# User.net
KiCad netlist of a schematic drawn in Altium Designer
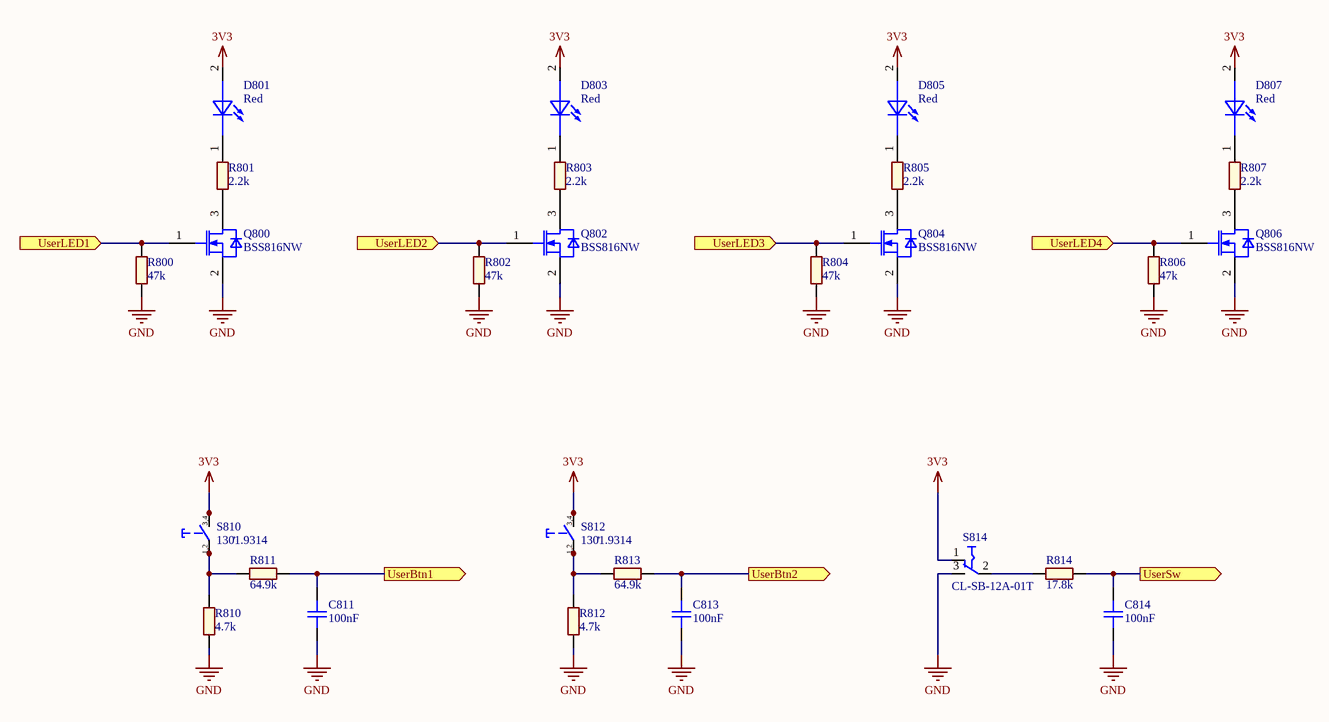
[diagram p0: User.SchDoc]

(export (version "E")
  (design (tool "Eeschema 10.0.6"))
  (components
    (comp (ref "C811")
      (value "100nF")
      (footprint "CAPC1608X90N-2")
      (description "CAP / CERA / 100nF / 50V / 10% / X7R (EIA) / -55°C to 125°C / 0603 / SMD / -")
      (fields (field (name "MANUFACTURER") "AVX"))
      (libsource (lib "PCBLibraryData") (part "CAP-SGL-STD-02P_00000001"))
    )
    (comp (ref "C813")
      (value "100nF")
      (footprint "CAPC1608X90N-2")
      (description "CAP / CERA / 100nF / 50V / 10% / X7R (EIA) / -55°C to 125°C / 0603 / SMD / -")
      (fields (field (name "MANUFACTURER") "AVX"))
      (libsource (lib "PCBLibraryData") (part "CAP-SGL-STD-02P_00000001"))
    )
    (comp (ref "C814")
      (value "100nF")
      (footprint "CAPC1608X90N-2")
      (description "CAP / CERA / 100nF / 50V / 10% / X7R (EIA) / -55°C to 125°C / 0603 / SMD / -")
      (fields (field (name "MANUFACTURER") "AVX"))
      (libsource (lib "PCBLibraryData") (part "CAP-SGL-STD-02P_00000001"))
    )
    (comp (ref "D801")
      (value "Red")
      (footprint "LEDSC160X80X80-2N-1")
      (description "WL-SMCW SMT Mono-color Chip LED Waterclear, Red,630nm")
      (fields (field (name "MANUFACTURER") "Wurth Elektronik"))
      (libsource (lib "PCBLibraryData") (part "d_led_a"))
    )
    (comp (ref "D803")
      (value "Red")
      (footprint "LEDSC160X80X80-2N-1")
      (description "WL-SMCW SMT Mono-color Chip LED Waterclear, Red,630nm")
      (fields (field (name "MANUFACTURER") "Wurth Elektronik"))
      (libsource (lib "PCBLibraryData") (part "d_led_a"))
    )
    (comp (ref "D805")
      (value "Red")
      (footprint "LEDSC160X80X80-2N-1")
      (description "WL-SMCW SMT Mono-color Chip LED Waterclear, Red,630nm")
      (fields (field (name "MANUFACTURER") "Wurth Elektronik"))
      (libsource (lib "PCBLibraryData") (part "d_led_a"))
    )
    (comp (ref "D807")
      (value "Red")
      (footprint "LEDSC160X80X80-2N-1")
      (description "WL-SMCW SMT Mono-color Chip LED Waterclear, Red,630nm")
      (fields (field (name "MANUFACTURER") "Wurth Elektronik"))
      (libsource (lib "PCBLibraryData") (part "d_led_a"))
    )
    (comp (ref "Q800")
      (value "BSS816NW")
      (footprint "SOT65P210X100-3N-1-V")
      (description "OptiMOS 2 Small-Signal-Transistor")
      (fields (field (name "MANUFACTURER") "Infineon Technologies"))
      (libsource (lib "PCBLibraryData") (part "igfet_n_ch_dep_dio_1g2s3d_3p"))
    )
    (comp (ref "Q802")
      (value "BSS816NW")
      (footprint "SOT65P210X100-3N-1-V")
      (description "OptiMOS 2 Small-Signal-Transistor")
      (fields (field (name "MANUFACTURER") "Infineon Technologies"))
      (libsource (lib "PCBLibraryData") (part "igfet_n_ch_dep_dio_1g2s3d_3p"))
    )
    (comp (ref "Q804")
      (value "BSS816NW")
      (footprint "SOT65P210X100-3N-1-V")
      (description "OptiMOS 2 Small-Signal-Transistor")
      (fields (field (name "MANUFACTURER") "Infineon Technologies"))
      (libsource (lib "PCBLibraryData") (part "igfet_n_ch_dep_dio_1g2s3d_3p"))
    )
    (comp (ref "Q806")
      (value "BSS816NW")
      (footprint "SOT65P210X100-3N-1-V")
      (description "OptiMOS 2 Small-Signal-Transistor")
      (fields (field (name "MANUFACTURER") "Infineon Technologies"))
      (libsource (lib "PCBLibraryData") (part "igfet_n_ch_dep_dio_1g2s3d_3p"))
    )
    (comp (ref "R800")
      (value "47k")
      (footprint "RESC1609X50N")
      (description "RES / STD / 47k / 100mW / 1% / 100ppm/K / -55°C to 155°C / 0603 / SMD / -")
      (fields (field (name "LEGACY PARTNUMBER") "RES01801333") (field (name "MANUFACTURER") "Vishay"))
      (libsource (lib "PCBLibraryData") (part "RES-SGL-STD-02P_00000006"))
    )
    (comp (ref "R801")
      (value "2.2k")
      (footprint "RESC1609X50N")
      (description "RES / STD / 2.2k / 100mW / 1% / 100ppm/K / -55°C to 155°C / 0603 / SMD / -")
      (fields (field (name "LEGACY PARTNUMBER") "RES01801179") (field (name "MANUFACTURER") "Vishay"))
      (libsource (lib "") (part "RES-SGL-STD-02P_00000006_2"))
    )
    (comp (ref "R802")
      (value "47k")
      (footprint "RESC1609X50N")
      (description "RES / STD / 47k / 100mW / 1% / 100ppm/K / -55°C to 155°C / 0603 / SMD / -")
      (fields (field (name "LEGACY PARTNUMBER") "RES01801333") (field (name "MANUFACTURER") "Vishay"))
      (libsource (lib "PCBLibraryData") (part "RES-SGL-STD-02P_00000006"))
    )
    (comp (ref "R803")
      (value "2.2k")
      (footprint "RESC1609X50N")
      (description "RES / STD / 2.2k / 100mW / 1% / 100ppm/K / -55°C to 155°C / 0603 / SMD / -")
      (fields (field (name "LEGACY PARTNUMBER") "RES01801179") (field (name "MANUFACTURER") "Vishay"))
      (libsource (lib "") (part "RES-SGL-STD-02P_00000006_2"))
    )
    (comp (ref "R804")
      (value "47k")
      (footprint "RESC1609X50N")
      (description "RES / STD / 47k / 100mW / 1% / 100ppm/K / -55°C to 155°C / 0603 / SMD / -")
      (fields (field (name "LEGACY PARTNUMBER") "RES01801333") (field (name "MANUFACTURER") "Vishay"))
      (libsource (lib "PCBLibraryData") (part "RES-SGL-STD-02P_00000006"))
    )
    (comp (ref "R805")
      (value "2.2k")
      (footprint "RESC1609X50N")
      (description "RES / STD / 2.2k / 100mW / 1% / 100ppm/K / -55°C to 155°C / 0603 / SMD / -")
      (fields (field (name "LEGACY PARTNUMBER") "RES01801179") (field (name "MANUFACTURER") "Vishay"))
      (libsource (lib "") (part "RES-SGL-STD-02P_00000006_2"))
    )
    (comp (ref "R806")
      (value "47k")
      (footprint "RESC1609X50N")
      (description "RES / STD / 47k / 100mW / 1% / 100ppm/K / -55°C to 155°C / 0603 / SMD / -")
      (fields (field (name "LEGACY PARTNUMBER") "RES01801333") (field (name "MANUFACTURER") "Vishay"))
      (libsource (lib "PCBLibraryData") (part "RES-SGL-STD-02P_00000006"))
    )
    (comp (ref "R807")
      (value "2.2k")
      (footprint "RESC1609X50N")
      (description "RES / STD / 2.2k / 100mW / 1% / 100ppm/K / -55°C to 155°C / 0603 / SMD / -")
      (fields (field (name "LEGACY PARTNUMBER") "RES01801179") (field (name "MANUFACTURER") "Vishay"))
      (libsource (lib "") (part "RES-SGL-STD-02P_00000006_2"))
    )
    (comp (ref "R810")
      (value "4.7k")
      (footprint "RESC1609X50N")
      (description "RES / STD / 4.7k / 100mW / 1% / 100ppm/K / -55°C to 155°C / 0603 / SMD / -")
      (fields (field (name "LEGACY PARTNUMBER") "RES01801219") (field (name "MANUFACTURER") "Vishay"))
      (libsource (lib "PCBLibraryData") (part "RES-SGL-STD-02P_00000006"))
    )
    (comp (ref "R811")
      (value "64.9k")
      (footprint "RESC1609X50N")
      (description "RES / STD / 64.9k / 100mW / 1% / 100ppm/K / -55°C to 155°C / 0603 / SMD / -")
      (fields (field (name "LEGACY PARTNUMBER") "RES01801350") (field (name "MANUFACTURER") "Vishay"))
      (libsource (lib "") (part "RES-SGL-STD-02P_00000006_1"))
    )
    (comp (ref "R812")
      (value "4.7k")
      (footprint "RESC1609X50N")
      (description "RES / STD / 4.7k / 100mW / 1% / 100ppm/K / -55°C to 155°C / 0603 / SMD / -")
      (fields (field (name "LEGACY PARTNUMBER") "RES01801219") (field (name "MANUFACTURER") "Vishay"))
      (libsource (lib "PCBLibraryData") (part "RES-SGL-STD-02P_00000006"))
    )
    (comp (ref "R813")
      (value "64.9k")
      (footprint "RESC1609X50N")
      (description "RES / STD / 64.9k / 100mW / 1% / 100ppm/K / -55°C to 155°C / 0603 / SMD / -")
      (fields (field (name "LEGACY PARTNUMBER") "RES01801350") (field (name "MANUFACTURER") "Vishay"))
      (libsource (lib "") (part "RES-SGL-STD-02P_00000006_1"))
    )
    (comp (ref "R814")
      (value "17.8k")
      (footprint "RESC1609X50N")
      (description "RES / STD / 17.8k / 100mW / 1% / 100ppm/K / -55°C to 155°C / 0603 / SMD / -")
      (fields (field (name "LEGACY PARTNUMBER") "RES01801283") (field (name "MANUFACTURER") "Vishay"))
      (libsource (lib "") (part "RES-SGL-STD-02P_00000006_1"))
    )
    (comp (ref "S810")
      (value "1301.9314")
      (footprint "SW-SMD-1301.9314")
      (description "Pushbutton Tactile Switch, Single Pole Single Throw, 4 Pins")
      (fields (field (name "LEGACY PARTNUMBER") "CON01500305") (field (name "MANUFACTURER") "Schurter"))
      (libsource (lib "PCBLibraryData") (part "sw_sr_no12_34_4p"))
    )
    (comp (ref "S812")
      (value "1301.9314")
      (footprint "SW-SMD-1301.9314")
      (description "Pushbutton Tactile Switch, Single Pole Single Throw, 4 Pins")
      (fields (field (name "LEGACY PARTNUMBER") "CON01500305") (field (name "MANUFACTURER") "Schurter"))
      (libsource (lib "PCBLibraryData") (part "sw_sr_no12_34_4p"))
    )
    (comp (ref "S814")
      (value "CL-SB-12A-01T")
      (footprint "SW-SMD-CL-SB-12A-01T")
      (description "Slid Switch, 12V, 200mA")
      (fields (field (name "MANUFACTURER") "NIDEC COPAL ELECTRONICS, Inc."))
      (libsource (lib "PCBLibraryData") (part "sw_co213_3p"))
    )
  )
  (nets
    (net (code "1") (name "/UserBtn1") (class "Default")
      (node (ref "C811") (pin "2") (pinfunction "2_2") (pintype "passive"))
      (node (ref "R811") (pin "1") (pinfunction "1_1") (pintype "passive"))
    )
    (net (code "2") (name "/UserBtn2") (class "Default")
      (node (ref "C813") (pin "2") (pinfunction "2_2") (pintype "passive"))
      (node (ref "R813") (pin "1") (pinfunction "1_1") (pintype "passive"))
    )
    (net (code "3") (name "/UserLED1") (class "Default")
      (node (ref "Q800") (pin "1") (pinfunction "GATE_1") (pintype "passive"))
      (node (ref "R800") (pin "2") (pinfunction "2_2") (pintype "passive"))
    )
    (net (code "4") (name "/UserLED2") (class "Default")
      (node (ref "Q802") (pin "1") (pinfunction "GATE_1") (pintype "passive"))
      (node (ref "R802") (pin "2") (pinfunction "2_2") (pintype "passive"))
    )
    (net (code "5") (name "/UserLED3") (class "Default")
      (node (ref "Q804") (pin "1") (pinfunction "GATE_1") (pintype "passive"))
      (node (ref "R804") (pin "2") (pinfunction "2_2") (pintype "passive"))
    )
    (net (code "6") (name "/UserLED4") (class "Default")
      (node (ref "Q806") (pin "1") (pinfunction "GATE_1") (pintype "passive"))
      (node (ref "R806") (pin "2") (pinfunction "2_2") (pintype "passive"))
    )
    (net (code "7") (name "/UserSw") (class "Default")
      (node (ref "C814") (pin "2") (pinfunction "2_2") (pintype "passive"))
      (node (ref "R814") (pin "1") (pinfunction "1_1") (pintype "passive"))
    )
    (net (code "8") (name "3V3") (class "Default")
      (node (ref "D801") (pin "2") (pinfunction "Anode_2") (pintype "passive"))
      (node (ref "D803") (pin "2") (pinfunction "Anode_2") (pintype "passive"))
      (node (ref "D805") (pin "2") (pinfunction "Anode_2") (pintype "passive"))
      (node (ref "D807") (pin "2") (pinfunction "Anode_2") (pintype "passive"))
      (node (ref "S810") (pin "3") (pinfunction "3_3") (pintype "passive"))
      (node (ref "S810") (pin "4") (pinfunction "4_4") (pintype "passive"))
      (node (ref "S812") (pin "3") (pinfunction "3_3") (pintype "passive"))
      (node (ref "S812") (pin "4") (pinfunction "4_4") (pintype "passive"))
      (node (ref "S814") (pin "1") (pinfunction "1_1") (pintype "passive"))
    )
    (net (code "9") (name "GND") (class "Default")
      (node (ref "C811") (pin "1") (pinfunction "1_1") (pintype "passive"))
      (node (ref "C813") (pin "1") (pinfunction "1_1") (pintype "passive"))
      (node (ref "C814") (pin "1") (pinfunction "1_1") (pintype "passive"))
      (node (ref "Q800") (pin "2") (pinfunction "SOURCE_2") (pintype "passive"))
      (node (ref "Q802") (pin "2") (pinfunction "SOURCE_2") (pintype "passive"))
      (node (ref "Q804") (pin "2") (pinfunction "SOURCE_2") (pintype "passive"))
      (node (ref "Q806") (pin "2") (pinfunction "SOURCE_2") (pintype "passive"))
      (node (ref "R800") (pin "1") (pinfunction "1_1") (pintype "passive"))
      (node (ref "R802") (pin "1") (pinfunction "1_1") (pintype "passive"))
      (node (ref "R804") (pin "1") (pinfunction "1_1") (pintype "passive"))
      (node (ref "R806") (pin "1") (pinfunction "1_1") (pintype "passive"))
      (node (ref "R810") (pin "1") (pinfunction "1_1") (pintype "passive"))
      (node (ref "R812") (pin "1") (pinfunction "1_1") (pintype "passive"))
      (node (ref "S814") (pin "3") (pinfunction "3_3") (pintype "passive"))
    )
    (net (code "10") (name "Net-(D801-Cathode)") (class "Default")
      (node (ref "D801") (pin "1") (pinfunction "Cathode_1") (pintype "passive"))
      (node (ref "R801") (pin "1") (pinfunction "1_1") (pintype "passive"))
    )
    (net (code "11") (name "Net-(D803-Cathode)") (class "Default")
      (node (ref "D803") (pin "1") (pinfunction "Cathode_1") (pintype "passive"))
      (node (ref "R803") (pin "1") (pinfunction "1_1") (pintype "passive"))
    )
    (net (code "12") (name "Net-(D805-Cathode)") (class "Default")
      (node (ref "D805") (pin "1") (pinfunction "Cathode_1") (pintype "passive"))
      (node (ref "R805") (pin "1") (pinfunction "1_1") (pintype "passive"))
    )
    (net (code "13") (name "Net-(D807-Cathode)") (class "Default")
      (node (ref "D807") (pin "1") (pinfunction "Cathode_1") (pintype "passive"))
      (node (ref "R807") (pin "1") (pinfunction "1_1") (pintype "passive"))
    )
    (net (code "14") (name "Net-(Q800-DRAIN)") (class "Default")
      (node (ref "Q800") (pin "3") (pinfunction "DRAIN_3") (pintype "passive"))
      (node (ref "R801") (pin "2") (pinfunction "2_2") (pintype "passive"))
    )
    (net (code "15") (name "Net-(Q802-DRAIN)") (class "Default")
      (node (ref "Q802") (pin "3") (pinfunction "DRAIN_3") (pintype "passive"))
      (node (ref "R803") (pin "2") (pinfunction "2_2") (pintype "passive"))
    )
    (net (code "16") (name "Net-(Q804-DRAIN)") (class "Default")
      (node (ref "Q804") (pin "3") (pinfunction "DRAIN_3") (pintype "passive"))
      (node (ref "R805") (pin "2") (pinfunction "2_2") (pintype "passive"))
    )
    (net (code "17") (name "Net-(Q806-DRAIN)") (class "Default")
      (node (ref "Q806") (pin "3") (pinfunction "DRAIN_3") (pintype "passive"))
      (node (ref "R807") (pin "2") (pinfunction "2_2") (pintype "passive"))
    )
    (net (code "18") (name "Net-(R810-Pad2)") (class "Default")
      (node (ref "R810") (pin "2") (pinfunction "2_2") (pintype "passive"))
      (node (ref "R811") (pin "2") (pinfunction "2_2") (pintype "passive"))
      (node (ref "S810") (pin "1") (pinfunction "1_1") (pintype "passive"))
      (node (ref "S810") (pin "2") (pinfunction "2_2") (pintype "passive"))
    )
    (net (code "19") (name "Net-(R812-Pad2)") (class "Default")
      (node (ref "R812") (pin "2") (pinfunction "2_2") (pintype "passive"))
      (node (ref "R813") (pin "2") (pinfunction "2_2") (pintype "passive"))
      (node (ref "S812") (pin "1") (pinfunction "1_1") (pintype "passive"))
      (node (ref "S812") (pin "2") (pinfunction "2_2") (pintype "passive"))
    )
    (net (code "20") (name "Net-(R814-Pad2)") (class "Default")
      (node (ref "R814") (pin "2") (pinfunction "2_2") (pintype "passive"))
      (node (ref "S814") (pin "2") (pinfunction "2_2") (pintype "passive"))
    )
  )
)
